# RF_AMP.net
KiCad netlist of a schematic drawn in Altium Designer
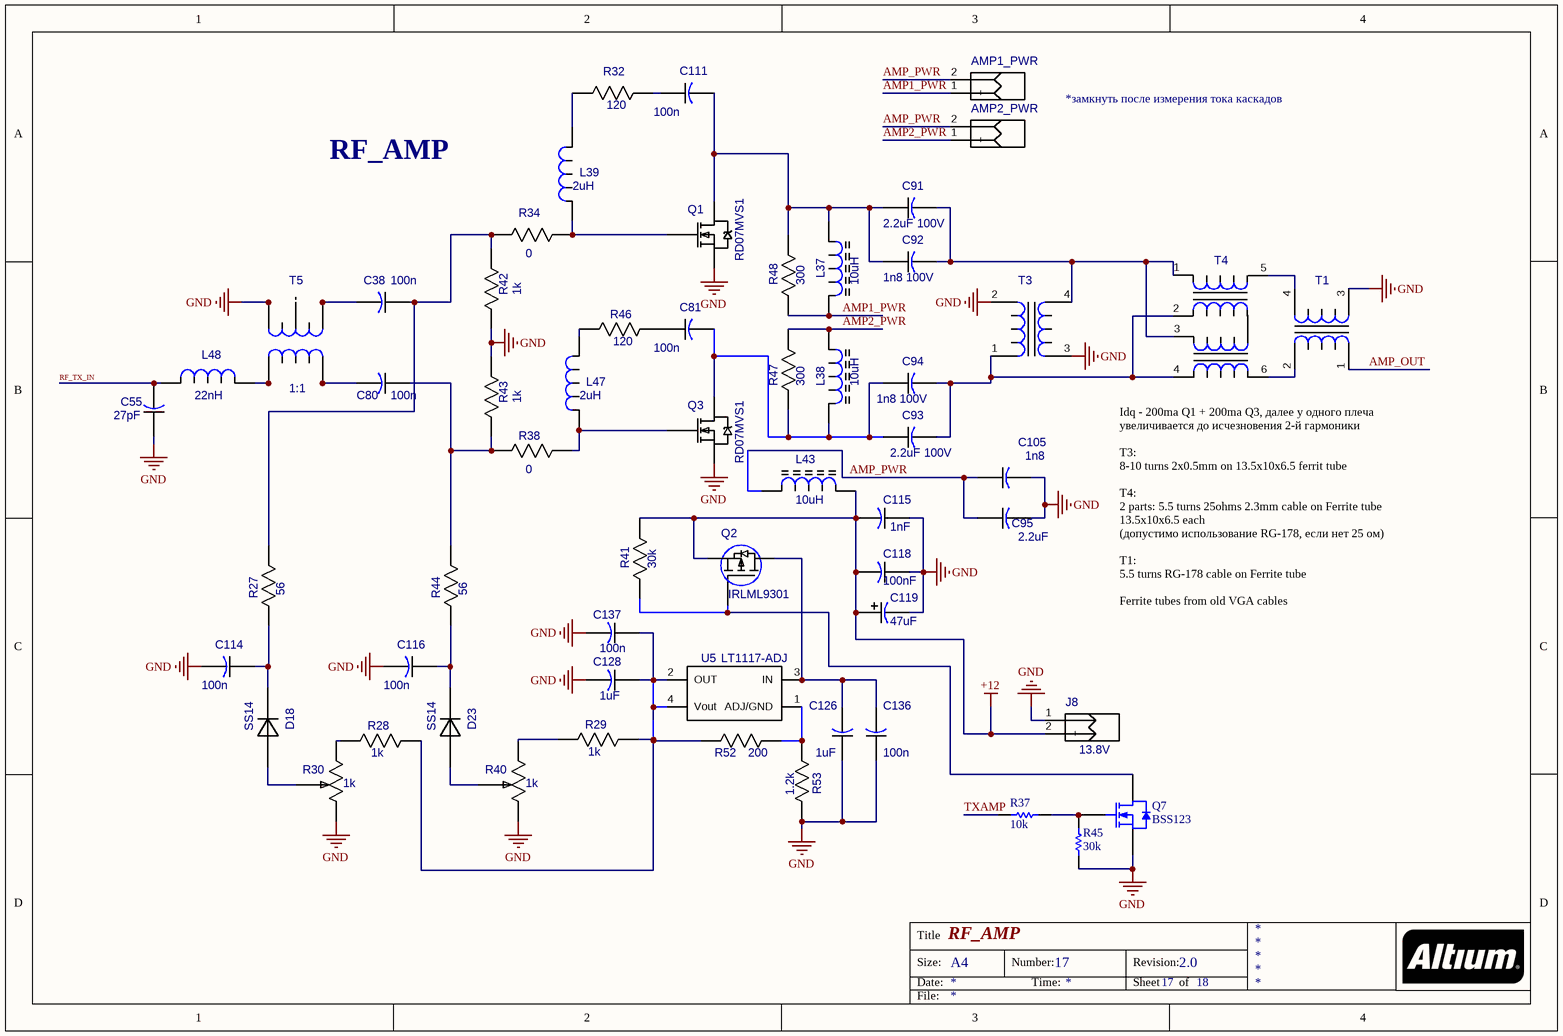
[diagram p0: RF_AMP.SchDoc]

(export (version "E")
  (design (tool "Eeschema 10.0.6"))
  (components
    (comp (ref "AMP1_PWR")
      (value "51022-0200")
      (footprint "51022-0200")
      (libsource (lib "*") (part "51022-0200"))
    )
    (comp (ref "AMP2_PWR")
      (value "51022-0200")
      (footprint "51022-0200")
      (libsource (lib "*") (part "51022-0200"))
    )
    (comp (ref "C38")
      (value "100n")
      (footprint "CAP_0805")
      (description "CAP_0805")
      (libsource (lib "*") (part "CAP_0805"))
    )
    (comp (ref "C55")
      (value "27pF")
      (footprint "CAP_0805")
      (description "CAP_0805")
      (libsource (lib "*") (part "CAP_0805"))
    )
    (comp (ref "C80")
      (value "100n")
      (footprint "CAP_0805")
      (description "CAP_0805")
      (libsource (lib "*") (part "CAP_0805"))
    )
    (comp (ref "C81")
      (value "100n")
      (footprint "CAP_1206")
      (description "CAP_1206")
      (libsource (lib "*") (part "CAP_1206"))
    )
    (comp (ref "C91")
      (value "2.2uF 100V")
      (footprint "CAP_1206")
      (description "CAP_1206")
      (libsource (lib "*") (part "CAP_1206"))
    )
    (comp (ref "C92")
      (value "1n8 100V")
      (footprint "CAP_1206")
      (description "CAP_1206")
      (libsource (lib "*") (part "CAP_1206"))
    )
    (comp (ref "C93")
      (value "2.2uF 100V")
      (footprint "CAP_1206")
      (description "CAP_1206")
      (libsource (lib "*") (part "CAP_1206"))
    )
    (comp (ref "C94")
      (value "1n8 100V")
      (footprint "CAP_1206")
      (description "CAP_1206")
      (libsource (lib "*") (part "CAP_1206"))
    )
    (comp (ref "C95")
      (value "2.2uF")
      (footprint "CAP_1206")
      (description "CAP_1206")
      (libsource (lib "*") (part "CAP_1206"))
    )
    (comp (ref "C105")
      (value "1n8")
      (footprint "CAP_1206")
      (description "CAP_1206")
      (libsource (lib "*") (part "CAP_1206"))
    )
    (comp (ref "C111")
      (value "100n")
      (footprint "CAP_1206")
      (description "CAP_1206")
      (libsource (lib "*") (part "CAP_1206"))
    )
    (comp (ref "C114")
      (value "100n")
      (footprint "CAP_0805")
      (description "CAP_0805")
      (libsource (lib "*") (part "CAP_0805"))
    )
    (comp (ref "C115")
      (value "1nF")
      (footprint "CAP_0805")
      (description "CAP_0805")
      (libsource (lib "*") (part "CAP_0805"))
    )
    (comp (ref "C116")
      (value "100n")
      (footprint "CAP_0805")
      (description "CAP_0805")
      (libsource (lib "*") (part "CAP_0805"))
    )
    (comp (ref "C118")
      (value "100nF")
      (footprint "CAP_0805")
      (description "CAP_0805")
      (libsource (lib "*") (part "CAP_0805"))
    )
    (comp (ref "C119")
      (value "47uF")
      (footprint "CAPAE_6.6x6.6h5.4")
      (description "CAPAE_6.6x6.6h5.4")
      (libsource (lib "*") (part "CAPAE_6.6x6.6h5.4"))
    )
    (comp (ref "C126")
      (value "1uF")
      (footprint "CAP_0805")
      (description "CAP_0805")
      (libsource (lib "*") (part "CAP_0805"))
    )
    (comp (ref "C128")
      (value "1uF")
      (footprint "CAP_0805")
      (description "CAP_0805")
      (libsource (lib "*") (part "CAP_0805"))
    )
    (comp (ref "C136")
      (value "100n")
      (footprint "CAP_0805")
      (description "CAP_0805")
      (libsource (lib "*") (part "CAP_0805"))
    )
    (comp (ref "C137")
      (value "100n")
      (footprint "CAP_0805")
      (description "CAP_0805")
      (libsource (lib "*") (part "CAP_0805"))
    )
    (comp (ref "D18") (value "SS14") (footprint "SS14") (libsource (lib "*") (part "SS14")))
    (comp (ref "D23") (value "SS14") (footprint "SS14") (libsource (lib "*") (part "SS14")))
    (comp (ref "J8")
      (value "13.8V")
      (footprint "1986717-2")
      (description "JX2")
      (libsource (lib "*") (part "1986717-2"))
    )
    (comp (ref "L37")
      (value "10uH")
      (footprint "IND_FERRITE_CORE")
      (description "Inductor")
      (libsource (lib "*") (part "IND_FERRITE_CORE"))
    )
    (comp (ref "L38")
      (value "10uH")
      (footprint "IND_FERRITE_CORE")
      (description "Inductor")
      (libsource (lib "*") (part "IND_FERRITE_CORE"))
    )
    (comp (ref "L39")
      (value "2uH")
      (footprint "IND_0805")
      (description "IND_0805")
      (libsource (lib "*") (part "IND_0805"))
    )
    (comp (ref "L43")
      (value "10uH")
      (footprint "IND_FERRITE_CORE")
      (description "Inductor")
      (libsource (lib "*") (part "IND_FERRITE_CORE"))
    )
    (comp (ref "L47")
      (value "2uH")
      (footprint "IND_0805")
      (description "IND_0805")
      (libsource (lib "*") (part "IND_0805"))
    )
    (comp (ref "L48")
      (value "22nH")
      (footprint "IND_0805")
      (description "IND_0805")
      (libsource (lib "*") (part "IND_0805"))
    )
    (comp (ref "Q1") (value "RD07MVS1") (footprint "RD07MVS1") (libsource (lib "*") (part "RD07MVS1")))
    (comp (ref "Q2")
      (value "IRLML9301")
      (footprint "SOT23")
      (description "MOSFET")
      (libsource (lib "*") (part "MOSFET_ENH_PD"))
    )
    (comp (ref "Q3") (value "RD07MVS1") (footprint "RD07MVS1") (libsource (lib "*") (part "RD07MVS1")))
    (comp (ref "Q7")
      (value "BSS123")
      (footprint "FAIR-SOT23-3_V")
      (fields (field (name "MANUFACTURER") "Fairchild"))
      (libsource (lib "Altium Content Vault") (part "NEMOS-GSD-3"))
    )
    (comp (ref "R27")
      (value "56")
      (footprint "RES_0805")
      (description "RES_0805")
      (libsource (lib "*") (part "RES_0805"))
    )
    (comp (ref "R28")
      (value "1k")
      (footprint "RES_0805")
      (description "RES_0805")
      (libsource (lib "*") (part "RES_0805"))
    )
    (comp (ref "R29")
      (value "1k")
      (footprint "RES_0805")
      (description "RES_0805")
      (libsource (lib "*") (part "RES_0805"))
    )
    (comp (ref "R30")
      (value "1k")
      (footprint "306J")
      (description "306J")
      (fields (field (name "Comment") "ADJ-1k"))
      (libsource (lib "*") (part "306J"))
    )
    (comp (ref "R32")
      (value "120")
      (footprint "RES_0805")
      (description "RES_0805")
      (libsource (lib "*") (part "RES_0805"))
    )
    (comp (ref "R34")
      (value "0")
      (footprint "RES_1206")
      (description "RES_1206")
      (libsource (lib "*") (part "RES_1206"))
    )
    (comp (ref "R37")
      (value "10k")
      (footprint "RESC2013X60X40NL20T25")
      (description "RES_0805")
      (fields (field (name "MANUFACTURER") "Panasonic") (field (name "PART NUMBER") "ERA-6AEB303V"))
      (libsource (lib "Altium Content Vault") (part "RES"))
    )
    (comp (ref "R38")
      (value "0")
      (footprint "RES_1206")
      (description "RES_1206")
      (libsource (lib "*") (part "RES_1206"))
    )
    (comp (ref "R40")
      (value "1k")
      (footprint "306J")
      (description "306J")
      (fields (field (name "Comment") "ADJ-1k"))
      (libsource (lib "*") (part "306J"))
    )
    (comp (ref "R41")
      (value "30k")
      (footprint "RES_0805")
      (description "RES_0805")
      (libsource (lib "*") (part "RES_0805"))
    )
    (comp (ref "R42")
      (value "1k")
      (footprint "RES_0805")
      (description "RES_0805")
      (libsource (lib "*") (part "RES_0805"))
    )
    (comp (ref "R43")
      (value "1k")
      (footprint "RES_0805")
      (description "RES_0805")
      (libsource (lib "*") (part "RES_0805"))
    )
    (comp (ref "R44")
      (value "56")
      (footprint "RES_0805")
      (description "RES_0805")
      (libsource (lib "*") (part "RES_0805"))
    )
    (comp (ref "R45")
      (value "30k")
      (footprint "RESC2013X60X40NL20T25")
      (description "RES_0805")
      (fields (field (name "MANUFACTURER") "Panasonic") (field (name "PART NUMBER") "ERA-6AEB303V"))
      (libsource (lib "Altium Content Vault") (part "RES"))
    )
    (comp (ref "R46")
      (value "120")
      (footprint "RES_0805")
      (description "RES_0805")
      (libsource (lib "*") (part "RES_0805"))
    )
    (comp (ref "R47")
      (value "300")
      (footprint "RES_1206")
      (description "RES_1206")
      (libsource (lib "*") (part "RES_1206"))
    )
    (comp (ref "R48")
      (value "300")
      (footprint "RES_1206")
      (description "RES_1206")
      (libsource (lib "*") (part "RES_1206"))
    )
    (comp (ref "R52")
      (value "200")
      (footprint "RES_0805")
      (description "RES_0805")
      (libsource (lib "*") (part "RES_0805"))
    )
    (comp (ref "R53")
      (value "1.2k")
      (footprint "RES_0805")
      (description "RES_0805")
      (libsource (lib "*") (part "RES_0805"))
    )
    (comp (ref "T1")
      (value "8T M2000HM 10*6*5")
      (footprint "Rutrof 2")
      (description "Transformer")
      (libsource (lib "*") (part "TRANSF_ICORE"))
    )
    (comp (ref "T3")
      (value "8T M2000HM 10*6*5")
      (footprint "Rutrof")
      (description "Transformer")
      (libsource (lib "*") (part "TRANSF_ICORE"))
    )
    (comp (ref "T4")
      (value "TRANSF_OUT")
      (footprint "TRANSF_OUT")
      (libsource (lib "RF-UNIT") (part "TRANSF_OUT_2"))
    )
    (comp (ref "T5")
      (value "1:1")
      (footprint "TRANSF_ACORE2")
      (libsource (lib "RF-UNIT_1") (part "TRANSF_ACORE2"))
    )
    (comp (ref "U5")
      (value "LT1117-ADJ")
      (footprint "LT1117IST-ADJ")
      (description "LT1117IST-ADJ")
      (libsource (lib "*") (part "LT1117IST-ADJ"))
    )
  )
  (nets
    (net (code "1") (name "+12") (class "Default")
      (node (ref "C115") (pin "2") (pinfunction "2_2") (pintype "passive"))
      (node (ref "C118") (pin "2") (pinfunction "2_2") (pintype "passive"))
      (node (ref "C119") (pin "1") (pinfunction "PLUS_1") (pintype "passive"))
      (node (ref "J8") (pin "2") (pinfunction "+_2") (pintype "passive"))
      (node (ref "L43") (pin "2") (pinfunction "B_2") (pintype "passive"))
      (node (ref "Q2") (pin "2") (pinfunction "S_2") (pintype "passive"))
      (node (ref "R41") (pin "2") (pinfunction "2_2") (pintype "passive"))
    )
    (net (code "2") (name "/AMP1_PWR") (class "Default")
      (node (ref "AMP1_PWR") (pin "1") (pinfunction "+_1") (pintype "passive"))
      (node (ref "L37") (pin "2") (pinfunction "B_2") (pintype "passive"))
      (node (ref "R48") (pin "1") (pinfunction "1_1") (pintype "passive"))
    )
    (net (code "3") (name "/AMP2_PWR") (class "Default")
      (node (ref "AMP2_PWR") (pin "1") (pinfunction "+_1") (pintype "passive"))
      (node (ref "L38") (pin "1") (pinfunction "A_1") (pintype "passive"))
      (node (ref "R47") (pin "2") (pinfunction "2_2") (pintype "passive"))
    )
    (net (code "4") (name "/AMP_OUT") (class "Default")
      (node (ref "T1") (pin "1") (pinfunction "P1_1") (pintype "passive"))
    )
    (net (code "5") (name "/AMP_PWR") (class "Default")
      (node (ref "AMP1_PWR") (pin "2") (pinfunction "-_2") (pintype "passive"))
      (node (ref "AMP2_PWR") (pin "2") (pinfunction "-_2") (pintype "passive"))
      (node (ref "C105") (pin "1") (pinfunction "1_1") (pintype "passive"))
      (node (ref "C95") (pin "1") (pinfunction "1_1") (pintype "passive"))
      (node (ref "L43") (pin "1") (pinfunction "A_1") (pintype "passive"))
    )
    (net (code "6") (name "/RF_TX_IN") (class "Default")
      (node (ref "C55") (pin "2") (pinfunction "2_2") (pintype "passive"))
      (node (ref "L48") (pin "1") (pinfunction "1_1") (pintype "passive"))
    )
    (net (code "7") (name "/TXAMP") (class "Default")
      (node (ref "R37") (pin "2") (pinfunction "2_2") (pintype "passive"))
    )
    (net (code "8") (name "GND") (class "Default")
      (node (ref "C105") (pin "2") (pinfunction "2_2") (pintype "passive"))
      (node (ref "C114") (pin "2") (pinfunction "2_2") (pintype "passive"))
      (node (ref "C115") (pin "1") (pinfunction "1_1") (pintype "passive"))
      (node (ref "C116") (pin "2") (pinfunction "2_2") (pintype "passive"))
      (node (ref "C118") (pin "1") (pinfunction "1_1") (pintype "passive"))
      (node (ref "C119") (pin "2") (pinfunction "MINUS_2") (pintype "passive"))
      (node (ref "C126") (pin "1") (pinfunction "1_1") (pintype "passive"))
      (node (ref "C128") (pin "2") (pinfunction "2_2") (pintype "passive"))
      (node (ref "C136") (pin "1") (pinfunction "1_1") (pintype "passive"))
      (node (ref "C137") (pin "2") (pinfunction "2_2") (pintype "passive"))
      (node (ref "C55") (pin "1") (pinfunction "1_1") (pintype "passive"))
      (node (ref "C95") (pin "2") (pinfunction "2_2") (pintype "passive"))
      (node (ref "J8") (pin "1") (pinfunction "-_1") (pintype "passive"))
      (node (ref "Q1") (pin "2") (pinfunction "S_2") (pintype "passive"))
      (node (ref "Q3") (pin "2") (pinfunction "S_2") (pintype "passive"))
      (node (ref "Q7") (pin "2") (pinfunction "S_2") (pintype "passive"))
      (node (ref "R30") (pin "1") (pinfunction "CCW_1") (pintype "passive"))
      (node (ref "R40") (pin "1") (pinfunction "CCW_1") (pintype "passive"))
      (node (ref "R42") (pin "1") (pinfunction "1_1") (pintype "passive"))
      (node (ref "R43") (pin "2") (pinfunction "2_2") (pintype "passive"))
      (node (ref "R45") (pin "1") (pinfunction "1_1") (pintype "passive"))
      (node (ref "R53") (pin "2") (pinfunction "2_2") (pintype "passive"))
      (node (ref "T1") (pin "3") (pinfunction "S1_3") (pintype "passive"))
      (node (ref "T3") (pin "2") (pinfunction "P2_2") (pintype "passive"))
      (node (ref "T3") (pin "3") (pinfunction "S1_3") (pintype "passive"))
      (node (ref "T5") (pin "3") (pinfunction "S3_3") (pintype "passive"))
      (node (ref "T5") (pin "9") (pinfunction "0_9") (pintype "passive"))
    )
    (net (code "9") (name "Net-(C38-Pad1)") (class "Default")
      (node (ref "C38") (pin "1") (pinfunction "1_1") (pintype "passive"))
      (node (ref "R27") (pin "2") (pinfunction "2_2") (pintype "passive"))
      (node (ref "R34") (pin "1") (pinfunction "1_1") (pintype "passive"))
      (node (ref "R42") (pin "2") (pinfunction "2_2") (pintype "passive"))
    )
    (net (code "10") (name "Net-(C80-Pad1)") (class "Default")
      (node (ref "C80") (pin "1") (pinfunction "1_1") (pintype "passive"))
      (node (ref "R38") (pin "1") (pinfunction "1_1") (pintype "passive"))
      (node (ref "R43") (pin "1") (pinfunction "1_1") (pintype "passive"))
      (node (ref "R44") (pin "2") (pinfunction "2_2") (pintype "passive"))
    )
    (net (code "11") (name "Net-(C81-Pad1)") (class "Default")
      (node (ref "C81") (pin "1") (pinfunction "1_1") (pintype "passive"))
      (node (ref "R46") (pin "2") (pinfunction "2_2") (pintype "passive"))
    )
    (net (code "12") (name "Net-(C111-Pad1)") (class "Default")
      (node (ref "C111") (pin "1") (pinfunction "1_1") (pintype "passive"))
      (node (ref "R32") (pin "2") (pinfunction "2_2") (pintype "passive"))
    )
    (net (code "13") (name "Net-(D18-A)") (class "Default")
      (node (ref "D18") (pin "2") (pinfunction "A_2") (pintype "passive"))
      (node (ref "R30") (pin "2") (pinfunction "W_2") (pintype "passive"))
    )
    (net (code "14") (name "Net-(D18-K)") (class "Default")
      (node (ref "C114") (pin "1") (pinfunction "1_1") (pintype "passive"))
      (node (ref "D18") (pin "1") (pinfunction "K_1") (pintype "passive"))
      (node (ref "R27") (pin "1") (pinfunction "1_1") (pintype "passive"))
    )
    (net (code "15") (name "Net-(D23-A)") (class "Default")
      (node (ref "D23") (pin "2") (pinfunction "A_2") (pintype "passive"))
      (node (ref "R40") (pin "2") (pinfunction "W_2") (pintype "passive"))
    )
    (net (code "16") (name "Net-(D23-K)") (class "Default")
      (node (ref "C116") (pin "1") (pinfunction "1_1") (pintype "passive"))
      (node (ref "D23") (pin "1") (pinfunction "K_1") (pintype "passive"))
      (node (ref "R44") (pin "1") (pinfunction "1_1") (pintype "passive"))
    )
    (net (code "17") (name "Net-(L37-A)") (class "Default")
      (node (ref "C111") (pin "2") (pinfunction "2_2") (pintype "passive"))
      (node (ref "C91") (pin "1") (pinfunction "1_1") (pintype "passive"))
      (node (ref "C92") (pin "1") (pinfunction "1_1") (pintype "passive"))
      (node (ref "L37") (pin "1") (pinfunction "A_1") (pintype "passive"))
      (node (ref "Q1") (pin "1") (pinfunction "D_1") (pintype "passive"))
      (node (ref "R48") (pin "2") (pinfunction "2_2") (pintype "passive"))
    )
    (net (code "18") (name "Net-(L38-B)") (class "Default")
      (node (ref "C81") (pin "2") (pinfunction "2_2") (pintype "passive"))
      (node (ref "C93") (pin "1") (pinfunction "1_1") (pintype "passive"))
      (node (ref "C94") (pin "1") (pinfunction "1_1") (pintype "passive"))
      (node (ref "L38") (pin "2") (pinfunction "B_2") (pintype "passive"))
      (node (ref "Q3") (pin "1") (pinfunction "D_1") (pintype "passive"))
      (node (ref "R47") (pin "1") (pinfunction "1_1") (pintype "passive"))
    )
    (net (code "19") (name "Net-(L39-Pad2)") (class "Default")
      (node (ref "L39") (pin "2") (pinfunction "2_2") (pintype "passive"))
      (node (ref "R32") (pin "1") (pinfunction "1_1") (pintype "passive"))
    )
    (net (code "20") (name "Net-(L47-Pad2)") (class "Default")
      (node (ref "L47") (pin "2") (pinfunction "2_2") (pintype "passive"))
      (node (ref "R46") (pin "1") (pinfunction "1_1") (pintype "passive"))
    )
    (net (code "21") (name "Net-(Q1-G)") (class "Default")
      (node (ref "L39") (pin "1") (pinfunction "1_1") (pintype "passive"))
      (node (ref "Q1") (pin "3") (pinfunction "G_3") (pintype "passive"))
      (node (ref "R34") (pin "2") (pinfunction "2_2") (pintype "passive"))
    )
    (net (code "22") (name "Net-(Q2-D)") (class "Default")
      (node (ref "C126") (pin "2") (pinfunction "2_2") (pintype "passive"))
      (node (ref "C136") (pin "2") (pinfunction "2_2") (pintype "passive"))
      (node (ref "Q2") (pin "3") (pinfunction "D_3") (pintype "passive"))
      (node (ref "U5") (pin "3") (pinfunction "IN_3") (pintype "passive"))
    )
    (net (code "23") (name "Net-(Q2-G)") (class "Default")
      (node (ref "Q2") (pin "1") (pinfunction "G_1") (pintype "passive"))
      (node (ref "Q7") (pin "3") (pinfunction "D_3") (pintype "passive"))
      (node (ref "R41") (pin "1") (pinfunction "1_1") (pintype "passive"))
    )
    (net (code "24") (name "Net-(Q3-G)") (class "Default")
      (node (ref "L47") (pin "1") (pinfunction "1_1") (pintype "passive"))
      (node (ref "Q3") (pin "3") (pinfunction "G_3") (pintype "passive"))
      (node (ref "R38") (pin "2") (pinfunction "2_2") (pintype "passive"))
    )
    (net (code "25") (name "Net-(Q7-G)") (class "Default")
      (node (ref "Q7") (pin "1") (pinfunction "G_1") (pintype "passive"))
      (node (ref "R37") (pin "1") (pinfunction "1_1") (pintype "passive"))
      (node (ref "R45") (pin "2") (pinfunction "2_2") (pintype "passive"))
    )
    (net (code "26") (name "Net-(R30-CW)") (class "Default")
      (node (ref "R28") (pin "1") (pinfunction "1_1") (pintype "passive"))
      (node (ref "R30") (pin "3") (pinfunction "CW_3") (pintype "passive"))
    )
    (net (code "27") (name "Net-(R40-CW)") (class "Default")
      (node (ref "R29") (pin "1") (pinfunction "1_1") (pintype "passive"))
      (node (ref "R40") (pin "3") (pinfunction "CW_3") (pintype "passive"))
    )
    (net (code "28") (name "Net-(T1-P2)") (class "Default")
      (node (ref "T1") (pin "2") (pinfunction "P2_2") (pintype "passive"))
      (node (ref "T4") (pin "6") (pinfunction "OUT2_6") (pintype "passive"))
    )
    (net (code "29") (name "Net-(T1-S2)") (class "Default")
      (node (ref "T1") (pin "4") (pinfunction "S2_4") (pintype "passive"))
      (node (ref "T4") (pin "5") (pinfunction "OUT1_5") (pintype "passive"))
    )
    (net (code "30") (name "Net-(T3-P1)") (class "Default")
      (node (ref "C93") (pin "2") (pinfunction "2_2") (pintype "passive"))
      (node (ref "C94") (pin "2") (pinfunction "2_2") (pintype "passive"))
      (node (ref "T3") (pin "1") (pinfunction "P1_1") (pintype "passive"))
      (node (ref "T4") (pin "2") (pinfunction "T1N_2") (pintype "passive"))
      (node (ref "T4") (pin "4") (pinfunction "T2P_4") (pintype "passive"))
    )
    (net (code "31") (name "Net-(T3-S2)") (class "Default")
      (node (ref "C91") (pin "2") (pinfunction "2_2") (pintype "passive"))
      (node (ref "C92") (pin "2") (pinfunction "2_2") (pintype "passive"))
      (node (ref "T3") (pin "4") (pinfunction "S2_4") (pintype "passive"))
      (node (ref "T4") (pin "1") (pinfunction "T1P_1") (pintype "passive"))
      (node (ref "T4") (pin "3") (pinfunction "T2N_3") (pintype "passive"))
    )
    (net (code "32") (name "Net-(T5-P1)") (class "Default")
      (node (ref "C80") (pin "2") (pinfunction "2_2") (pintype "passive"))
      (node (ref "T5") (pin "10") (pinfunction "0_10") (pintype "passive"))
      (node (ref "T5") (pin "6") (pinfunction "P1_6") (pintype "passive"))
    )
    (net (code "33") (name "Net-(T5-P2)") (class "Default")
      (node (ref "L48") (pin "2") (pinfunction "2_2") (pintype "passive"))
      (node (ref "T5") (pin "11") (pinfunction "0_11") (pintype "passive"))
      (node (ref "T5") (pin "4") (pinfunction "P2_4") (pintype "passive"))
    )
    (net (code "34") (name "Net-(T5-S1)") (class "Default")
      (node (ref "C38") (pin "2") (pinfunction "2_2") (pintype "passive"))
      (node (ref "T5") (pin "1") (pinfunction "S1_1") (pintype "passive"))
      (node (ref "T5") (pin "7") (pinfunction "0_7") (pintype "passive"))
    )
    (net (code "35") (name "Net-(U5-ADJ{slash}GND)") (class "Default")
      (node (ref "R52") (pin "2") (pinfunction "2_2") (pintype "passive"))
      (node (ref "R53") (pin "1") (pinfunction "1_1") (pintype "passive"))
      (node (ref "U5") (pin "1") (pinfunction "ADJ/GND_1") (pintype "passive"))
    )
    (net (code "36") (name "Net-(U5-OUT)") (class "Default")
      (node (ref "C128") (pin "1") (pinfunction "1_1") (pintype "passive"))
      (node (ref "C137") (pin "1") (pinfunction "1_1") (pintype "passive"))
      (node (ref "R28") (pin "2") (pinfunction "2_2") (pintype "passive"))
      (node (ref "R29") (pin "2") (pinfunction "2_2") (pintype "passive"))
      (node (ref "R52") (pin "1") (pinfunction "1_1") (pintype "passive"))
      (node (ref "U5") (pin "2") (pinfunction "OUT_2") (pintype "passive"))
      (node (ref "U5") (pin "4") (pinfunction "Vout_4") (pintype "passive"))
    )
    (net (code "37") (name "unconnected-(T5-S2-Pad2)") (class "Default")
      (node (ref "T5") (pin "2") (pinfunction "S2_2") (pintype "passive"))
    )
    (net (code "38") (name "unconnected-(T5-S2-Pad8)") (class "Default")
      (node (ref "T5") (pin "8") (pinfunction "S2_8") (pintype "passive"))
    )
  )
)
